# lipo-battery.net
KiCad netlist of a schematic drawn in EAGLE
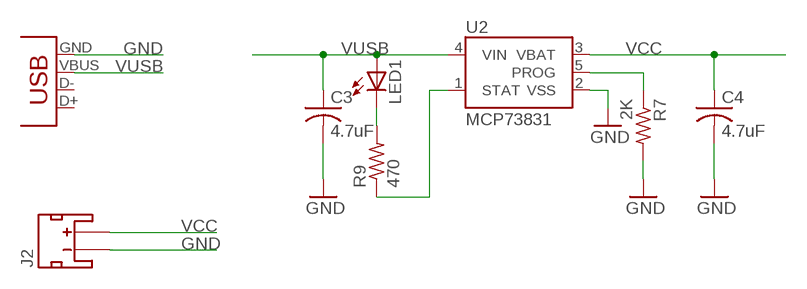
[diagram p0: schematic, sheet 1]

(export (version "E")
  (design (tool "Eeschema 10.0.6"))
  (components
    (comp (ref "C3")
      (value "4.7uF")
      (footprint "eagle-import:C1206")
      (libsource (lib "eagle-import") (part "C-USC1206"))
    )
    (comp (ref "C4")
      (value "4.7uF")
      (footprint "eagle-import:C1206")
      (libsource (lib "eagle-import") (part "C-USC1206"))
    )
    (comp (ref "J2")
      (value "JST_2MM_MALE")
      (footprint "eagle-import:JST-2-SMD")
      (libsource (lib "eagle-import") (part "JST_2MM_MALE"))
    )
    (comp (ref "JP1")
      (value "USB-B-VERTICAL")
      (footprint "eagle-import:USB_MINIB_VERTICAL")
      (libsource (lib "eagle-import") (part "USB-B-VERTICAL"))
    )
    (comp (ref "LED1")
      (value "LEDSMT1206")
      (footprint "eagle-import:1206")
      (libsource (lib "eagle-import") (part "LEDSMT1206"))
    )
    (comp (ref "R7")
      (value "2K")
      (footprint "eagle-import:R1206")
      (libsource (lib "eagle-import") (part "R-US_R1206"))
    )
    (comp (ref "R9")
      (value "470")
      (footprint "eagle-import:R1206")
      (libsource (lib "eagle-import") (part "R-US_R1206"))
    )
    (comp (ref "U2")
      (value "MCP73831")
      (footprint "eagle-import:SOT23-5")
      (libsource (lib "eagle-import") (part "MCP73831"))
    )
  )
  (nets
    (net (code "1") (name "/VCC") (class "Default")
      (node (ref "C4") (pin "1") (pinfunction "1_1") (pintype "passive"))
      (node (ref "J2") (pin "2") (pinfunction "+_2") (pintype "bidirectional"))
      (node (ref "U2") (pin "3") (pinfunction "VBAT_3") (pintype "power_in"))
    )
    (net (code "2") (name "/VUSB") (class "Default")
      (node (ref "C3") (pin "1") (pinfunction "1_1") (pintype "passive"))
      (node (ref "JP1") (pin "VBUS") (pinfunction "VBUS_VBUS") (pintype "bidirectional"))
      (node (ref "LED1") (pin "A") (pinfunction "A_A") (pintype "passive"))
      (node (ref "U2") (pin "4") (pinfunction "VIN_4") (pintype "power_in"))
    )
    (net (code "3") (name "GND") (class "Default")
      (node (ref "C3") (pin "2") (pinfunction "2_2") (pintype "passive"))
      (node (ref "C4") (pin "2") (pinfunction "2_2") (pintype "passive"))
      (node (ref "J2") (pin "1") (pinfunction "-_1") (pintype "bidirectional"))
      (node (ref "JP1") (pin "GND") (pinfunction "GND_GND") (pintype "bidirectional"))
      (node (ref "R7") (pin "2") (pinfunction "2_2") (pintype "passive"))
      (node (ref "U2") (pin "2") (pinfunction "VSS_2") (pintype "power_in"))
    )
    (net (code "4") (name "Net-(LED1-PadC)") (class "Default")
      (node (ref "LED1") (pin "C") (pinfunction "C_C") (pintype "passive"))
      (node (ref "R9") (pin "2") (pinfunction "2_2") (pintype "passive"))
    )
    (net (code "5") (name "Net-(U2-PROG)") (class "Default")
      (node (ref "R7") (pin "1") (pinfunction "1_1") (pintype "passive"))
      (node (ref "U2") (pin "5") (pinfunction "PROG_5") (pintype "input"))
    )
    (net (code "6") (name "Net-(U2-STAT)") (class "Default")
      (node (ref "R9") (pin "1") (pinfunction "1_1") (pintype "passive"))
      (node (ref "U2") (pin "1") (pinfunction "STAT_1") (pintype "output"))
    )
    (net (code "7") (name "unconnected-(J2-PAD1-PadNC1)") (class "Default")
      (node (ref "J2") (pin "NC1") (pinfunction "PAD1_NC1") (pintype "bidirectional"))
    )
    (net (code "8") (name "unconnected-(J2-PAD2-PadNC2)") (class "Default")
      (node (ref "J2") (pin "NC2") (pinfunction "PAD2_NC2") (pintype "bidirectional"))
    )
    (net (code "9") (name "unconnected-(JP1-PadD+)") (class "Default")
      (node (ref "JP1") (pin "D+") (pinfunction "D+_D+") (pintype "bidirectional"))
    )
    (net (code "10") (name "unconnected-(JP1-PadD-)") (class "Default")
      (node (ref "JP1") (pin "D-") (pinfunction "D-_D-") (pintype "bidirectional"))
    )
  )
)
